# M3_Chip.net
KiCad netlist of a schematic drawn in Altium Designer
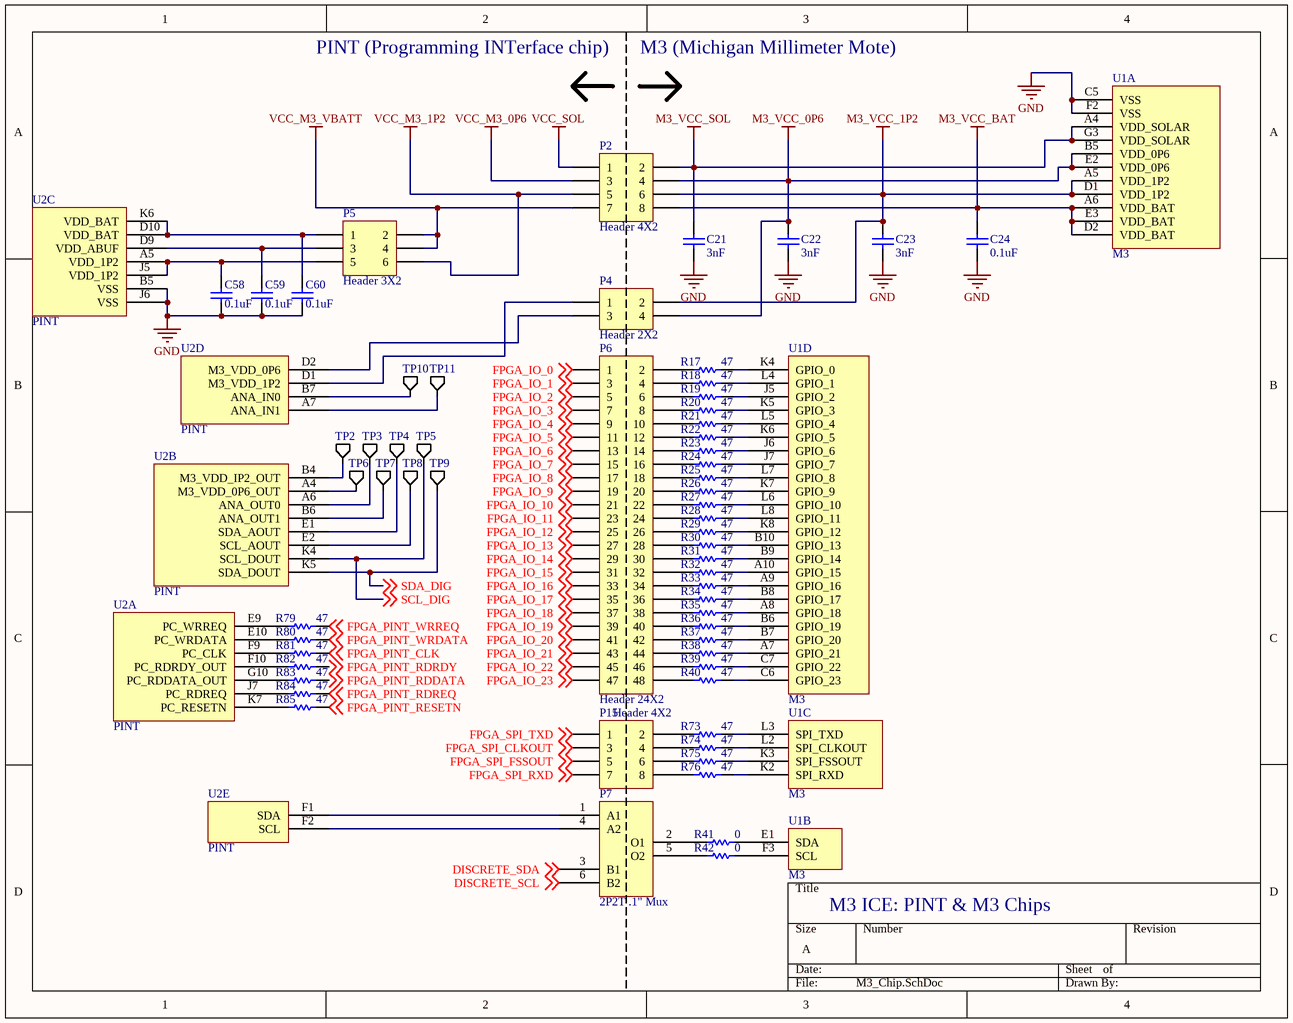
[diagram p0: M3_Chip.SchDoc]

(export (version "E")
  (design (tool "Eeschema 10.0.6"))
  (components
    (comp (ref "C21")
      (value "3nF")
      (footprint "1608[0603]")
      (description "Capacitor (Semiconductor SIM Model)")
      (fields
        (field (name "DISTPARTNO") "399-7893-1-ND")
        (field (name "MANPARTNO") "C0603C302K5GACTU")
        (field (name "PUBLISHER") "Altium Limited")
      )
      (libsource (lib "Miscellaneous Devices") (part "Cap Semi"))
    )
    (comp (ref "C22")
      (value "3nF")
      (footprint "1608[0603]")
      (description "Capacitor (Semiconductor SIM Model)")
      (fields
        (field (name "DISTPARTNO") "399-7893-1-ND")
        (field (name "MANPARTNO") "C0603C302K5GACTU")
        (field (name "PUBLISHER") "Altium Limited")
      )
      (libsource (lib "Miscellaneous Devices") (part "Cap Semi"))
    )
    (comp (ref "C23")
      (value "3nF")
      (footprint "1608[0603]")
      (description "Capacitor (Semiconductor SIM Model)")
      (fields
        (field (name "DISTPARTNO") "399-7893-1-ND")
        (field (name "MANPARTNO") "C0603C302K5GACTU")
        (field (name "PUBLISHER") "Altium Limited")
      )
      (libsource (lib "Miscellaneous Devices") (part "Cap Semi"))
    )
    (comp (ref "C24")
      (value "0.1uF")
      (footprint "1608[0603]")
      (description "Capacitor (Semiconductor SIM Model)")
      (fields
        (field (name "DISTPARTNO") "445-1317-1-ND")
        (field (name "MANPARTNO") "C1608X7R1C104K")
        (field (name "PUBLISHER") "Altium Limited")
      )
      (libsource (lib "Miscellaneous Devices") (part "Cap Semi"))
    )
    (comp (ref "C58")
      (value "0.1uF")
      (footprint "1608[0603]")
      (description "Capacitor (Semiconductor SIM Model)")
      (fields
        (field (name "DISTPARTNO") "445-1317-1-ND")
        (field (name "MANPARTNO") "C1608X7R1C104K")
        (field (name "PUBLISHER") "Altium Limited")
      )
      (libsource (lib "Miscellaneous Devices") (part "Cap Semi"))
    )
    (comp (ref "C59")
      (value "0.1uF")
      (footprint "1608[0603]")
      (description "Capacitor (Semiconductor SIM Model)")
      (fields
        (field (name "DISTPARTNO") "445-1317-1-ND")
        (field (name "MANPARTNO") "C1608X7R1C104K")
        (field (name "PUBLISHER") "Altium Limited")
      )
      (libsource (lib "Miscellaneous Devices") (part "Cap Semi"))
    )
    (comp (ref "C60")
      (value "0.1uF")
      (footprint "1608[0603]")
      (description "Capacitor (Semiconductor SIM Model)")
      (fields
        (field (name "DISTPARTNO") "445-1317-1-ND")
        (field (name "MANPARTNO") "C1608X7R1C104K")
        (field (name "PUBLISHER") "Altium Limited")
      )
      (libsource (lib "Miscellaneous Devices") (part "Cap Semi"))
    )
    (comp (ref "P2")
      (value "Header 4X2")
      (footprint "HDR2X4")
      (description "Header, 4-Pin, Dual row")
      (fields
        (field (name "DISTPARTNO") "A26530-40-ND")
        (field (name "MANPARTNO") "4-103328-0")
        (field (name "PUBLISHER") "Altium Limited")
      )
      (libsource (lib "Miscellaneous Connectors") (part "Header 4X2"))
    )
    (comp (ref "P4")
      (value "Header 2X2")
      (footprint "HDR2X2")
      (description "Header, 2-Pin, Dual row")
      (fields (field (name "PUBLISHER") "Altium Limited"))
      (libsource (lib "Miscellaneous Connectors") (part "Header 2X2"))
    )
    (comp (ref "P5")
      (value "Header 3X2")
      (footprint "HDR2X3")
      (description "Header, 3-Pin, Dual row")
      (fields (field (name "PUBLISHER") "Altium Limited"))
      (libsource (lib "Miscellaneous Connectors") (part "Header 3X2"))
    )
    (comp (ref "P6")
      (value "Header 24X2")
      (footprint "HDR2X24")
      (description "Header, 24-Pin, Dual row")
      (fields
        (field (name "DISTPARTNO") "A26530-40-ND")
        (field (name "MANPARTNO") "4-103328-0")
        (field (name "PUBLISHER") "Altium Limited")
      )
      (libsource (lib "Miscellaneous Connectors") (part "Header 24X2"))
    )
    (comp (ref "P7")
      (value "2P2T .1\" Mux")
      (footprint "HDR3x2")
      (libsource (lib "M3") (part "2P2T .1{dblquote} Mux"))
    )
    (comp (ref "P15")
      (value "Header 4X2")
      (footprint "HDR2X4")
      (description "Header, 4-Pin, Dual row")
      (fields (field (name "PUBLISHER") "Altium Limited"))
      (libsource (lib "Miscellaneous Connectors") (part "Header 4X2"))
    )
    (comp (ref "R17")
      (value "47")
      (footprint "0603")
      (description "Semiconductor Resistor")
      (fields
        (field (name "DISTPARTNO") "P47GCT-ND")
        (field (name "MANPARTNO") "ERJ-3GEYJ470V")
        (field (name "PUBLISHER") "Altium Limited")
      )
      (libsource (lib "M3") (part "Res Chip"))
    )
    (comp (ref "R18")
      (value "47")
      (footprint "0603")
      (description "Semiconductor Resistor")
      (fields
        (field (name "DISTPARTNO") "P47GCT-ND")
        (field (name "MANPARTNO") "ERJ-3GEYJ470V")
        (field (name "PUBLISHER") "Altium Limited")
      )
      (libsource (lib "M3") (part "Res Chip"))
    )
    (comp (ref "R19")
      (value "47")
      (footprint "0603")
      (description "Semiconductor Resistor")
      (fields
        (field (name "DISTPARTNO") "P47GCT-ND")
        (field (name "MANPARTNO") "ERJ-3GEYJ470V")
        (field (name "PUBLISHER") "Altium Limited")
      )
      (libsource (lib "M3") (part "Res Chip"))
    )
    (comp (ref "R20")
      (value "47")
      (footprint "0603")
      (description "Semiconductor Resistor")
      (fields
        (field (name "DISTPARTNO") "P47GCT-ND")
        (field (name "MANPARTNO") "ERJ-3GEYJ470V")
        (field (name "PUBLISHER") "Altium Limited")
      )
      (libsource (lib "M3") (part "Res Chip"))
    )
    (comp (ref "R21")
      (value "47")
      (footprint "0603")
      (description "Semiconductor Resistor")
      (fields
        (field (name "DISTPARTNO") "P47GCT-ND")
        (field (name "MANPARTNO") "ERJ-3GEYJ470V")
        (field (name "PUBLISHER") "Altium Limited")
      )
      (libsource (lib "M3") (part "Res Chip"))
    )
    (comp (ref "R22")
      (value "47")
      (footprint "0603")
      (description "Semiconductor Resistor")
      (fields
        (field (name "DISTPARTNO") "P47GCT-ND")
        (field (name "MANPARTNO") "ERJ-3GEYJ470V")
        (field (name "PUBLISHER") "Altium Limited")
      )
      (libsource (lib "M3") (part "Res Chip"))
    )
    (comp (ref "R23")
      (value "47")
      (footprint "0603")
      (description "Semiconductor Resistor")
      (fields
        (field (name "DISTPARTNO") "P47GCT-ND")
        (field (name "MANPARTNO") "ERJ-3GEYJ470V")
        (field (name "PUBLISHER") "Altium Limited")
      )
      (libsource (lib "M3") (part "Res Chip"))
    )
    (comp (ref "R24")
      (value "47")
      (footprint "0603")
      (description "Semiconductor Resistor")
      (fields
        (field (name "DISTPARTNO") "P47GCT-ND")
        (field (name "MANPARTNO") "ERJ-3GEYJ470V")
        (field (name "PUBLISHER") "Altium Limited")
      )
      (libsource (lib "M3") (part "Res Chip"))
    )
    (comp (ref "R25")
      (value "47")
      (footprint "0603")
      (description "Semiconductor Resistor")
      (fields
        (field (name "DISTPARTNO") "P47GCT-ND")
        (field (name "MANPARTNO") "ERJ-3GEYJ470V")
        (field (name "PUBLISHER") "Altium Limited")
      )
      (libsource (lib "M3") (part "Res Chip"))
    )
    (comp (ref "R26")
      (value "47")
      (footprint "0603")
      (description "Semiconductor Resistor")
      (fields
        (field (name "DISTPARTNO") "P47GCT-ND")
        (field (name "MANPARTNO") "ERJ-3GEYJ470V")
        (field (name "PUBLISHER") "Altium Limited")
      )
      (libsource (lib "M3") (part "Res Chip"))
    )
    (comp (ref "R27")
      (value "47")
      (footprint "0603")
      (description "Semiconductor Resistor")
      (fields
        (field (name "DISTPARTNO") "P47GCT-ND")
        (field (name "MANPARTNO") "ERJ-3GEYJ470V")
        (field (name "PUBLISHER") "Altium Limited")
      )
      (libsource (lib "M3") (part "Res Chip"))
    )
    (comp (ref "R28")
      (value "47")
      (footprint "0603")
      (description "Semiconductor Resistor")
      (fields
        (field (name "DISTPARTNO") "P47GCT-ND")
        (field (name "MANPARTNO") "ERJ-3GEYJ470V")
        (field (name "PUBLISHER") "Altium Limited")
      )
      (libsource (lib "M3") (part "Res Chip"))
    )
    (comp (ref "R29")
      (value "47")
      (footprint "0603")
      (description "Semiconductor Resistor")
      (fields
        (field (name "DISTPARTNO") "P47GCT-ND")
        (field (name "MANPARTNO") "ERJ-3GEYJ470V")
        (field (name "PUBLISHER") "Altium Limited")
      )
      (libsource (lib "M3") (part "Res Chip"))
    )
    (comp (ref "R30")
      (value "47")
      (footprint "0603")
      (description "Semiconductor Resistor")
      (fields
        (field (name "DISTPARTNO") "P47GCT-ND")
        (field (name "MANPARTNO") "ERJ-3GEYJ470V")
        (field (name "PUBLISHER") "Altium Limited")
      )
      (libsource (lib "M3") (part "Res Chip"))
    )
    (comp (ref "R31")
      (value "47")
      (footprint "0603")
      (description "Semiconductor Resistor")
      (fields
        (field (name "DISTPARTNO") "P47GCT-ND")
        (field (name "MANPARTNO") "ERJ-3GEYJ470V")
        (field (name "PUBLISHER") "Altium Limited")
      )
      (libsource (lib "M3") (part "Res Chip"))
    )
    (comp (ref "R32")
      (value "47")
      (footprint "0603")
      (description "Semiconductor Resistor")
      (fields
        (field (name "DISTPARTNO") "P47GCT-ND")
        (field (name "MANPARTNO") "ERJ-3GEYJ470V")
        (field (name "PUBLISHER") "Altium Limited")
      )
      (libsource (lib "M3") (part "Res Chip"))
    )
    (comp (ref "R33")
      (value "47")
      (footprint "0603")
      (description "Semiconductor Resistor")
      (fields
        (field (name "DISTPARTNO") "P47GCT-ND")
        (field (name "MANPARTNO") "ERJ-3GEYJ470V")
        (field (name "PUBLISHER") "Altium Limited")
      )
      (libsource (lib "M3") (part "Res Chip"))
    )
    (comp (ref "R34")
      (value "47")
      (footprint "0603")
      (description "Semiconductor Resistor")
      (fields
        (field (name "DISTPARTNO") "P47GCT-ND")
        (field (name "MANPARTNO") "ERJ-3GEYJ470V")
        (field (name "PUBLISHER") "Altium Limited")
      )
      (libsource (lib "M3") (part "Res Chip"))
    )
    (comp (ref "R35")
      (value "47")
      (footprint "0603")
      (description "Semiconductor Resistor")
      (fields
        (field (name "DISTPARTNO") "P47GCT-ND")
        (field (name "MANPARTNO") "ERJ-3GEYJ470V")
        (field (name "PUBLISHER") "Altium Limited")
      )
      (libsource (lib "M3") (part "Res Chip"))
    )
    (comp (ref "R36")
      (value "47")
      (footprint "0603")
      (description "Semiconductor Resistor")
      (fields
        (field (name "DISTPARTNO") "P47GCT-ND")
        (field (name "MANPARTNO") "ERJ-3GEYJ470V")
        (field (name "PUBLISHER") "Altium Limited")
      )
      (libsource (lib "M3") (part "Res Chip"))
    )
    (comp (ref "R37")
      (value "47")
      (footprint "0603")
      (description "Semiconductor Resistor")
      (fields
        (field (name "DISTPARTNO") "P47GCT-ND")
        (field (name "MANPARTNO") "ERJ-3GEYJ470V")
        (field (name "PUBLISHER") "Altium Limited")
      )
      (libsource (lib "M3") (part "Res Chip"))
    )
    (comp (ref "R38")
      (value "47")
      (footprint "0603")
      (description "Semiconductor Resistor")
      (fields
        (field (name "DISTPARTNO") "P47GCT-ND")
        (field (name "MANPARTNO") "ERJ-3GEYJ470V")
        (field (name "PUBLISHER") "Altium Limited")
      )
      (libsource (lib "M3") (part "Res Chip"))
    )
    (comp (ref "R39")
      (value "47")
      (footprint "0603")
      (description "Semiconductor Resistor")
      (fields
        (field (name "DISTPARTNO") "P47GCT-ND")
        (field (name "MANPARTNO") "ERJ-3GEYJ470V")
        (field (name "PUBLISHER") "Altium Limited")
      )
      (libsource (lib "M3") (part "Res Chip"))
    )
    (comp (ref "R40")
      (value "47")
      (footprint "0603")
      (description "Semiconductor Resistor")
      (fields
        (field (name "DISTPARTNO") "P47GCT-ND")
        (field (name "MANPARTNO") "ERJ-3GEYJ470V")
        (field (name "PUBLISHER") "Altium Limited")
      )
      (libsource (lib "M3") (part "Res Chip"))
    )
    (comp (ref "R41")
      (value "0")
      (footprint "0603")
      (description "Semiconductor Resistor")
      (fields
        (field (name "DISTPARTNO") "P0.0GCT-ND")
        (field (name "MANPARTNO") "ERJ-3GEY0R00V")
        (field (name "PUBLISHER") "Altium Limited")
      )
      (libsource (lib "M3") (part "Res Chip"))
    )
    (comp (ref "R42")
      (value "0")
      (footprint "0603")
      (description "Semiconductor Resistor")
      (fields
        (field (name "DISTPARTNO") "P0.0GCT-ND")
        (field (name "MANPARTNO") "ERJ-3GEY0R00V")
        (field (name "PUBLISHER") "Altium Limited")
      )
      (libsource (lib "M3") (part "Res Chip"))
    )
    (comp (ref "R73")
      (value "47")
      (footprint "0603")
      (description "Semiconductor Resistor")
      (fields
        (field (name "DISTPARTNO") "P47GCT-ND")
        (field (name "MANPARTNO") "ERJ-3GEYJ470V")
        (field (name "PUBLISHER") "Altium Limited")
      )
      (libsource (lib "M3") (part "Res Chip"))
    )
    (comp (ref "R74")
      (value "47")
      (footprint "0603")
      (description "Semiconductor Resistor")
      (fields
        (field (name "DISTPARTNO") "P47GCT-ND")
        (field (name "MANPARTNO") "ERJ-3GEYJ470V")
        (field (name "PUBLISHER") "Altium Limited")
      )
      (libsource (lib "M3") (part "Res Chip"))
    )
    (comp (ref "R75")
      (value "47")
      (footprint "0603")
      (description "Semiconductor Resistor")
      (fields
        (field (name "DISTPARTNO") "P47GCT-ND")
        (field (name "MANPARTNO") "ERJ-3GEYJ470V")
        (field (name "PUBLISHER") "Altium Limited")
      )
      (libsource (lib "M3") (part "Res Chip"))
    )
    (comp (ref "R76")
      (value "47")
      (footprint "0603")
      (description "Semiconductor Resistor")
      (fields
        (field (name "DISTPARTNO") "P47GCT-ND")
        (field (name "MANPARTNO") "ERJ-3GEYJ470V")
        (field (name "PUBLISHER") "Altium Limited")
      )
      (libsource (lib "M3") (part "Res Chip"))
    )
    (comp (ref "R79")
      (value "47")
      (footprint "0603")
      (description "Semiconductor Resistor")
      (fields
        (field (name "DISTPARTNO") "P47GCT-ND")
        (field (name "MANPARTNO") "ERJ-3GEYJ470V")
        (field (name "PUBLISHER") "Altium Limited")
      )
      (libsource (lib "M3") (part "Res Chip"))
    )
    (comp (ref "R80")
      (value "47")
      (footprint "0603")
      (description "Semiconductor Resistor")
      (fields
        (field (name "DISTPARTNO") "P47GCT-ND")
        (field (name "MANPARTNO") "ERJ-3GEYJ470V")
        (field (name "PUBLISHER") "Altium Limited")
      )
      (libsource (lib "M3") (part "Res Chip"))
    )
    (comp (ref "R81")
      (value "47")
      (footprint "0603")
      (description "Semiconductor Resistor")
      (fields
        (field (name "DISTPARTNO") "P47GCT-ND")
        (field (name "MANPARTNO") "ERJ-3GEYJ470V")
        (field (name "PUBLISHER") "Altium Limited")
      )
      (libsource (lib "M3") (part "Res Chip"))
    )
    (comp (ref "R82")
      (value "47")
      (footprint "0603")
      (description "Semiconductor Resistor")
      (fields
        (field (name "DISTPARTNO") "P47GCT-ND")
        (field (name "MANPARTNO") "ERJ-3GEYJ470V")
        (field (name "PUBLISHER") "Altium Limited")
      )
      (libsource (lib "M3") (part "Res Chip"))
    )
    (comp (ref "R83")
      (value "47")
      (footprint "0603")
      (description "Semiconductor Resistor")
      (fields
        (field (name "DISTPARTNO") "P47GCT-ND")
        (field (name "MANPARTNO") "ERJ-3GEYJ470V")
        (field (name "PUBLISHER") "Altium Limited")
      )
      (libsource (lib "M3") (part "Res Chip"))
    )
    (comp (ref "R84")
      (value "47")
      (footprint "0603")
      (description "Semiconductor Resistor")
      (fields
        (field (name "DISTPARTNO") "P47GCT-ND")
        (field (name "MANPARTNO") "ERJ-3GEYJ470V")
        (field (name "PUBLISHER") "Altium Limited")
      )
      (libsource (lib "M3") (part "Res Chip"))
    )
    (comp (ref "R85")
      (value "47")
      (footprint "0603")
      (description "Semiconductor Resistor")
      (fields
        (field (name "DISTPARTNO") "P47GCT-ND")
        (field (name "MANPARTNO") "ERJ-3GEYJ470V")
        (field (name "PUBLISHER") "Altium Limited")
      )
      (libsource (lib "M3") (part "Res Chip"))
    )
    (comp (ref "TP2") (value "TP") (footprint "TP") (libsource (lib "M3") (part "TP")))
    (comp (ref "TP3") (value "TP") (footprint "TP") (libsource (lib "M3") (part "TP")))
    (comp (ref "TP4") (value "TP") (footprint "TP") (libsource (lib "M3") (part "TP")))
    (comp (ref "TP5") (value "TP") (footprint "TP") (libsource (lib "M3") (part "TP")))
    (comp (ref "TP6") (value "TP") (footprint "TP") (libsource (lib "M3") (part "TP")))
    (comp (ref "TP7") (value "TP") (footprint "TP") (libsource (lib "M3") (part "TP")))
    (comp (ref "TP8") (value "TP") (footprint "TP") (libsource (lib "M3") (part "TP")))
    (comp (ref "TP9") (value "TP") (footprint "TP") (libsource (lib "M3") (part "TP")))
    (comp (ref "TP10") (value "TP") (footprint "TP") (libsource (lib "M3") (part "TP")))
    (comp (ref "TP11") (value "TP") (footprint "TP") (libsource (lib "M3") (part "TP")))
    (comp (ref "U1")
      (value "M3")
      (footprint "CPGA-84")
      (fields (field (name "DISTPARTNO") "3M5067-ND") (field (name "MANPARTNO") "200-6311-9UN-1900"))
      (libsource (lib "M3") (part "M3"))
    )
    (comp (ref "U2")
      (value "PINT")
      (footprint "CPGA-65")
      (fields (field (name "DISTPARTNO") "3M5066-ND") (field (name "MANPARTNO") "200-6310-9UN-1900"))
      (libsource (lib "M3") (part "PINT"))
    )
  )
  (nets
    (net (code "1") (name "DISCRETE_SCL") (class "Default")
      (node (ref "P7") (pin "6") (pinfunction "B2_6") (pintype "passive"))
    )
    (net (code "2") (name "DISCRETE_SDA") (class "Default")
      (node (ref "P7") (pin "3") (pinfunction "B1_3") (pintype "passive"))
    )
    (net (code "3") (name "FPGA_IO_0") (class "Default")
      (node (ref "P6") (pin "1") (pinfunction "1_1") (pintype "passive"))
    )
    (net (code "4") (name "FPGA_IO_1") (class "Default")
      (node (ref "P6") (pin "3") (pinfunction "3_3") (pintype "passive"))
    )
    (net (code "5") (name "FPGA_IO_2") (class "Default")
      (node (ref "P6") (pin "5") (pinfunction "5_5") (pintype "passive"))
    )
    (net (code "6") (name "FPGA_IO_3") (class "Default")
      (node (ref "P6") (pin "7") (pinfunction "7_7") (pintype "passive"))
    )
    (net (code "7") (name "FPGA_IO_4") (class "Default")
      (node (ref "P6") (pin "9") (pinfunction "9_9") (pintype "passive"))
    )
    (net (code "8") (name "FPGA_IO_5") (class "Default")
      (node (ref "P6") (pin "11") (pinfunction "11_11") (pintype "passive"))
    )
    (net (code "9") (name "FPGA_IO_6") (class "Default")
      (node (ref "P6") (pin "13") (pinfunction "13_13") (pintype "passive"))
    )
    (net (code "10") (name "FPGA_IO_7") (class "Default")
      (node (ref "P6") (pin "15") (pinfunction "15_15") (pintype "passive"))
    )
    (net (code "11") (name "FPGA_IO_8") (class "Default")
      (node (ref "P6") (pin "17") (pinfunction "17_17") (pintype "passive"))
    )
    (net (code "12") (name "FPGA_IO_9") (class "Default")
      (node (ref "P6") (pin "19") (pinfunction "19_19") (pintype "passive"))
    )
    (net (code "13") (name "FPGA_IO_10") (class "Default")
      (node (ref "P6") (pin "21") (pinfunction "21_21") (pintype "passive"))
    )
    (net (code "14") (name "FPGA_IO_11") (class "Default")
      (node (ref "P6") (pin "23") (pinfunction "23_23") (pintype "passive"))
    )
    (net (code "15") (name "FPGA_IO_12") (class "Default")
      (node (ref "P6") (pin "25") (pinfunction "25_25") (pintype "passive"))
    )
    (net (code "16") (name "FPGA_IO_13") (class "Default")
      (node (ref "P6") (pin "27") (pinfunction "27_27") (pintype "passive"))
    )
    (net (code "17") (name "FPGA_IO_14") (class "Default")
      (node (ref "P6") (pin "29") (pinfunction "29_29") (pintype "passive"))
    )
    (net (code "18") (name "FPGA_IO_15") (class "Default")
      (node (ref "P6") (pin "31") (pinfunction "31_31") (pintype "passive"))
    )
    (net (code "19") (name "FPGA_IO_16") (class "Default")
      (node (ref "P6") (pin "33") (pinfunction "33_33") (pintype "passive"))
    )
    (net (code "20") (name "FPGA_IO_17") (class "Default")
      (node (ref "P6") (pin "35") (pinfunction "35_35") (pintype "passive"))
    )
    (net (code "21") (name "FPGA_IO_18") (class "Default")
      (node (ref "P6") (pin "37") (pinfunction "37_37") (pintype "passive"))
    )
    (net (code "22") (name "FPGA_IO_19") (class "Default")
      (node (ref "P6") (pin "39") (pinfunction "39_39") (pintype "passive"))
    )
    (net (code "23") (name "FPGA_IO_20") (class "Default")
      (node (ref "P6") (pin "41") (pinfunction "41_41") (pintype "passive"))
    )
    (net (code "24") (name "FPGA_IO_21") (class "Default")
      (node (ref "P6") (pin "43") (pinfunction "43_43") (pintype "passive"))
    )
    (net (code "25") (name "FPGA_IO_22") (class "Default")
      (node (ref "P6") (pin "45") (pinfunction "45_45") (pintype "passive"))
    )
    (net (code "26") (name "FPGA_IO_23") (class "Default")
      (node (ref "P6") (pin "47") (pinfunction "47_47") (pintype "passive"))
    )
    (net (code "27") (name "FPGA_PINT_CLK") (class "Default")
      (node (ref "R81") (pin "1") (pinfunction "1_1") (pintype "passive"))
    )
    (net (code "28") (name "FPGA_PINT_RDDATA") (class "Default")
      (node (ref "R83") (pin "1") (pinfunction "1_1") (pintype "passive"))
    )
    (net (code "29") (name "FPGA_PINT_RDRDY") (class "Default")
      (node (ref "R82") (pin "1") (pinfunction "1_1") (pintype "passive"))
    )
    (net (code "30") (name "FPGA_PINT_RDREQ") (class "Default")
      (node (ref "R84") (pin "1") (pinfunction "1_1") (pintype "passive"))
    )
    (net (code "31") (name "FPGA_PINT_RESETN") (class "Default")
      (node (ref "R85") (pin "1") (pinfunction "1_1") (pintype "passive"))
    )
    (net (code "32") (name "FPGA_PINT_WRDATA") (class "Default")
      (node (ref "R80") (pin "1") (pinfunction "1_1") (pintype "passive"))
    )
    (net (code "33") (name "FPGA_PINT_WRREQ") (class "Default")
      (node (ref "R79") (pin "1") (pinfunction "1_1") (pintype "passive"))
    )
    (net (code "34") (name "FPGA_SPI_CLKOUT") (class "Default")
      (node (ref "P15") (pin "3") (pinfunction "3_3") (pintype "passive"))
    )
    (net (code "35") (name "FPGA_SPI_FSSOUT") (class "Default")
      (node (ref "P15") (pin "5") (pinfunction "5_5") (pintype "passive"))
    )
    (net (code "36") (name "FPGA_SPI_RXD") (class "Default")
      (node (ref "P15") (pin "7") (pinfunction "7_7") (pintype "passive"))
    )
    (net (code "37") (name "FPGA_SPI_TXD") (class "Default")
      (node (ref "P15") (pin "1") (pinfunction "1_1") (pintype "passive"))
    )
    (net (code "38") (name "GND") (class "Default")
      (node (ref "C21") (pin "1") (pinfunction "1_1") (pintype "passive"))
      (node (ref "C22") (pin "1") (pinfunction "1_1") (pintype "passive"))
      (node (ref "C23") (pin "1") (pinfunction "1_1") (pintype "passive"))
      (node (ref "C24") (pin "1") (pinfunction "1_1") (pintype "passive"))
      (node (ref "C58") (pin "1") (pinfunction "1_1") (pintype "passive"))
      (node (ref "C59") (pin "1") (pinfunction "1_1") (pintype "passive"))
      (node (ref "C60") (pin "1") (pinfunction "1_1") (pintype "passive"))
      (node (ref "U1") (pin "C5") (pinfunction "VSS_C5") (pintype "passive"))
      (node (ref "U1") (pin "F2") (pinfunction "VSS_F2") (pintype "passive"))
      (node (ref "U2") (pin "B5") (pinfunction "VSS_B5") (pintype "passive"))
      (node (ref "U2") (pin "J6") (pinfunction "VSS_J6") (pintype "passive"))
    )
    (net (code "39") (name "M3_VCC_0P6") (class "Default")
      (node (ref "C22") (pin "2") (pinfunction "2_2") (pintype "passive"))
      (node (ref "P2") (pin "4") (pinfunction "4_4") (pintype "passive"))
      (node (ref "P4") (pin "4") (pinfunction "4_4") (pintype "passive"))
      (node (ref "U1") (pin "B5") (pinfunction "VDD_0P6_B5") (pintype "passive"))
      (node (ref "U1") (pin "E2") (pinfunction "VDD_0P6_E2") (pintype "passive"))
    )
    (net (code "40") (name "M3_VCC_1P2") (class "Default")
      (node (ref "C23") (pin "2") (pinfunction "2_2") (pintype "passive"))
      (node (ref "P2") (pin "6") (pinfunction "6_6") (pintype "passive"))
      (node (ref "P4") (pin "2") (pinfunction "2_2") (pintype "passive"))
      (node (ref "U1") (pin "A5") (pinfunction "VDD_1P2_A5") (pintype "passive"))
      (node (ref "U1") (pin "D1") (pinfunction "VDD_1P2_D1") (pintype "passive"))
    )
    (net (code "41") (name "M3_VCC_BAT") (class "Default")
      (node (ref "C24") (pin "2") (pinfunction "2_2") (pintype "passive"))
      (node (ref "P2") (pin "8") (pinfunction "8_8") (pintype "passive"))
      (node (ref "U1") (pin "A6") (pinfunction "VDD_BAT_A6") (pintype "passive"))
      (node (ref "U1") (pin "D2") (pinfunction "VDD_BAT_D2") (pintype "passive"))
      (node (ref "U1") (pin "E3") (pinfunction "VDD_BAT_E3") (pintype "passive"))
    )
    (net (code "42") (name "M3_VCC_SOL") (class "Default")
      (node (ref "C21") (pin "2") (pinfunction "2_2") (pintype "passive"))
      (node (ref "P2") (pin "2") (pinfunction "2_2") (pintype "passive"))
      (node (ref "U1") (pin "A4") (pinfunction "VDD_SOLAR_A4") (pintype "passive"))
      (node (ref "U1") (pin "G3") (pinfunction "VDD_SOLAR_G3") (pintype "passive"))
    )
    (net (code "43") (name "Net-(C58-Pad2)") (class "Default")
      (node (ref "C58") (pin "2") (pinfunction "2_2") (pintype "passive"))
      (node (ref "P5") (pin "5") (pinfunction "5_5") (pintype "passive"))
      (node (ref "U2") (pin "A5") (pinfunction "VDD_1P2_A5") (pintype "passive"))
      (node (ref "U2") (pin "J5") (pinfunction "VDD_1P2_J5") (pintype "passive"))
    )
    (net (code "44") (name "Net-(C60-Pad2)") (class "Default")
      (node (ref "C60") (pin "2") (pinfunction "2_2") (pintype "passive"))
      (node (ref "P5") (pin "1") (pinfunction "1_1") (pintype "passive"))
      (node (ref "U2") (pin "D10") (pinfunction "VDD_BAT_D10") (pintype "passive"))
      (node (ref "U2") (pin "K6") (pinfunction "VDD_BAT_K6") (pintype "passive"))
    )
    (net (code "45") (name "Net-(P6-Pad2)") (class "Default")
      (node (ref "P6") (pin "2") (pinfunction "2_2") (pintype "passive"))
      (node (ref "R17") (pin "2") (pinfunction "2_2") (pintype "passive"))
    )
    (net (code "46") (name "Net-(P6-Pad4)") (class "Default")
      (node (ref "P6") (pin "4") (pinfunction "4_4") (pintype "passive"))
      (node (ref "R18") (pin "2") (pinfunction "2_2") (pintype "passive"))
    )
    (net (code "47") (name "Net-(P6-Pad6)") (class "Default")
      (node (ref "P6") (pin "6") (pinfunction "6_6") (pintype "passive"))
      (node (ref "R19") (pin "2") (pinfunction "2_2") (pintype "passive"))
    )
    (net (code "48") (name "Net-(P6-Pad8)") (class "Default")
      (node (ref "P6") (pin "8") (pinfunction "8_8") (pintype "passive"))
      (node (ref "R20") (pin "2") (pinfunction "2_2") (pintype "passive"))
    )
    (net (code "49") (name "Net-(P6-Pad10)") (class "Default")
      (node (ref "P6") (pin "10") (pinfunction "10_10") (pintype "passive"))
      (node (ref "R21") (pin "2") (pinfunction "2_2") (pintype "passive"))
    )
    (net (code "50") (name "Net-(P6-Pad12)") (class "Default")
      (node (ref "P6") (pin "12") (pinfunction "12_12") (pintype "passive"))
      (node (ref "R22") (pin "2") (pinfunction "2_2") (pintype "passive"))
    )
    (net (code "51") (name "Net-(P6-Pad14)") (class "Default")
      (node (ref "P6") (pin "14") (pinfunction "14_14") (pintype "passive"))
      (node (ref "R23") (pin "2") (pinfunction "2_2") (pintype "passive"))
    )
    (net (code "52") (name "Net-(P6-Pad16)") (class "Default")
      (node (ref "P6") (pin "16") (pinfunction "16_16") (pintype "passive"))
      (node (ref "R24") (pin "2") (pinfunction "2_2") (pintype "passive"))
    )
    (net (code "53") (name "Net-(P6-Pad18)") (class "Default")
      (node (ref "P6") (pin "18") (pinfunction "18_18") (pintype "passive"))
      (node (ref "R25") (pin "2") (pinfunction "2_2") (pintype "passive"))
    )
    (net (code "54") (name "Net-(P6-Pad20)") (class "Default")
      (node (ref "P6") (pin "20") (pinfunction "20_20") (pintype "passive"))
      (node (ref "R26") (pin "2") (pinfunction "2_2") (pintype "passive"))
    )
    (net (code "55") (name "Net-(P6-Pad22)") (class "Default")
      (node (ref "P6") (pin "22") (pinfunction "22_22") (pintype "passive"))
      (node (ref "R27") (pin "2") (pinfunction "2_2") (pintype "passive"))
    )
    (net (code "56") (name "Net-(P6-Pad24)") (class "Default")
      (node (ref "P6") (pin "24") (pinfunction "24_24") (pintype "passive"))
      (node (ref "R28") (pin "2") (pinfunction "2_2") (pintype "passive"))
    )
    (net (code "57") (name "Net-(P6-Pad26)") (class "Default")
      (node (ref "P6") (pin "26") (pinfunction "26_26") (pintype "passive"))
      (node (ref "R29") (pin "2") (pinfunction "2_2") (pintype "passive"))
    )
    (net (code "58") (name "Net-(P6-Pad28)") (class "Default")
      (node (ref "P6") (pin "28") (pinfunction "28_28") (pintype "passive"))
      (node (ref "R30") (pin "2") (pinfunction "2_2") (pintype "passive"))
    )
    (net (code "59") (name "Net-(P6-Pad30)") (class "Default")
      (node (ref "P6") (pin "30") (pinfunction "30_30") (pintype "passive"))
      (node (ref "R31") (pin "2") (pinfunction "2_2") (pintype "passive"))
    )
    (net (code "60") (name "Net-(P6-Pad32)") (class "Default")
      (node (ref "P6") (pin "32") (pinfunction "32_32") (pintype "passive"))
      (node (ref "R32") (pin "2") (pinfunction "2_2") (pintype "passive"))
    )
    (net (code "61") (name "Net-(P6-Pad34)") (class "Default")
      (node (ref "P6") (pin "34") (pinfunction "34_34") (pintype "passive"))
      (node (ref "R33") (pin "2") (pinfunction "2_2") (pintype "passive"))
    )
    (net (code "62") (name "Net-(P6-Pad36)") (class "Default")
      (node (ref "P6") (pin "36") (pinfunction "36_36") (pintype "passive"))
      (node (ref "R34") (pin "2") (pinfunction "2_2") (pintype "passive"))
    )
    (net (code "63") (name "Net-(P6-Pad38)") (class "Default")
      (node (ref "P6") (pin "38") (pinfunction "38_38") (pintype "passive"))
      (node (ref "R35") (pin "2") (pinfunction "2_2") (pintype "passive"))
    )
    (net (code "64") (name "Net-(P6-Pad40)") (class "Default")
      (node (ref "P6") (pin "40") (pinfunction "40_40") (pintype "passive"))
      (node (ref "R36") (pin "2") (pinfunction "2_2") (pintype "passive"))
    )
    (net (code "65") (name "Net-(P6-Pad42)") (class "Default")
      (node (ref "P6") (pin "42") (pinfunction "42_42") (pintype "passive"))
      (node (ref "R37") (pin "2") (pinfunction "2_2") (pintype "passive"))
    )
    (net (code "66") (name "Net-(P6-Pad44)") (class "Default")
      (node (ref "P6") (pin "44") (pinfunction "44_44") (pintype "passive"))
      (node (ref "R38") (pin "2") (pinfunction "2_2") (pintype "passive"))
    )
    (net (code "67") (name "Net-(P6-Pad46)") (class "Default")
      (node (ref "P6") (pin "46") (pinfunction "46_46") (pintype "passive"))
      (node (ref "R39") (pin "2") (pinfunction "2_2") (pintype "passive"))
    )
    (net (code "68") (name "Net-(P6-Pad48)") (class "Default")
      (node (ref "P6") (pin "48") (pinfunction "48_48") (pintype "passive"))
      (node (ref "R40") (pin "2") (pinfunction "2_2") (pintype "passive"))
    )
    (net (code "69") (name "Net-(P7-A1)") (class "Default")
      (node (ref "P7") (pin "1") (pinfunction "A1_1") (pintype "passive"))
      (node (ref "U2") (pin "F1") (pinfunction "SDA_F1") (pintype "passive"))
    )
    (net (code "70") (name "Net-(P7-A2)") (class "Default")
      (node (ref "P7") (pin "4") (pinfunction "A2_4") (pintype "passive"))
      (node (ref "U2") (pin "F2") (pinfunction "SCL_F2") (pintype "passive"))
    )
    (net (code "71") (name "Net-(P7-O1)") (class "Default")
      (node (ref "P7") (pin "2") (pinfunction "O1_2") (pintype "passive"))
      (node (ref "R41") (pin "2") (pinfunction "2_2") (pintype "passive"))
    )
    (net (code "72") (name "Net-(P7-O2)") (class "Default")
      (node (ref "P7") (pin "5") (pinfunction "O2_5") (pintype "passive"))
      (node (ref "R42") (pin "2") (pinfunction "2_2") (pintype "passive"))
    )
    (net (code "73") (name "Net-(P15-Pad2)") (class "Default")
      (node (ref "P15") (pin "2") (pinfunction "2_2") (pintype "passive"))
      (node (ref "R73") (pin "2") (pinfunction "2_2") (pintype "passive"))
    )
    (net (code "74") (name "Net-(P15-Pad4)") (class "Default")
      (node (ref "P15") (pin "4") (pinfunction "4_4") (pintype "passive"))
      (node (ref "R74") (pin "2") (pinfunction "2_2") (pintype "passive"))
    )
    (net (code "75") (name "Net-(P15-Pad6)") (class "Default")
      (node (ref "P15") (pin "6") (pinfunction "6_6") (pintype "passive"))
      (node (ref "R75") (pin "2") (pinfunction "2_2") (pintype "passive"))
    )
    (net (code "76") (name "Net-(P15-Pad8)") (class "Default")
      (node (ref "P15") (pin "8") (pinfunction "8_8") (pintype "passive"))
      (node (ref "R76") (pin "2") (pinfunction "2_2") (pintype "passive"))
    )
    (net (code "77") (name "Net-(TP2-A)") (class "Default")
      (node (ref "TP2") (pin "1") (pinfunction "A_1") (pintype "passive"))
      (node (ref "U2") (pin "B4") (pinfunction "M3_VDD_IP2_OUT_B4") (pintype "passive"))
    )
    (net (code "78") (name "Net-(TP3-A)") (class "Default")
      (node (ref "TP3") (pin "1") (pinfunction "A_1") (pintype "passive"))
      (node (ref "U2") (pin "A6") (pinfunction "ANA_OUT0_A6") (pintype "passive"))
    )
    (net (code "79") (name "Net-(TP4-A)") (class "Default")
      (node (ref "TP4") (pin "1") (pinfunction "A_1") (pintype "passive"))
      (node (ref "U2") (pin "E1") (pinfunction "SDA_AOUT_E1") (pintype "passive"))
    )
    (net (code "80") (name "Net-(TP6-A)") (class "Default")
      (node (ref "TP6") (pin "1") (pinfunction "A_1") (pintype "passive"))
      (node (ref "U2") (pin "A4") (pinfunction "M3_VDD_0P6_OUT_A4") (pintype "passive"))
    )
    (net (code "81") (name "Net-(TP7-A)") (class "Default")
      (node (ref "TP7") (pin "1") (pinfunction "A_1") (pintype "passive"))
      (node (ref "U2") (pin "B6") (pinfunction "ANA_OUT1_B6") (pintype "passive"))
    )
    (net (code "82") (name "Net-(TP8-A)") (class "Default")
      (node (ref "TP8") (pin "1") (pinfunction "A_1") (pintype "passive"))
      (node (ref "U2") (pin "E2") (pinfunction "SCL_AOUT_E2") (pintype "passive"))
    )
    (net (code "83") (name "Net-(TP10-A)") (class "Default")
      (node (ref "TP10") (pin "1") (pinfunction "A_1") (pintype "passive"))
      (node (ref "U2") (pin "B7") (pinfunction "ANA_IN0_B7") (pintype "passive"))
    )
    (net (code "84") (name "Net-(TP11-A)") (class "Default")
      (node (ref "TP11") (pin "1") (pinfunction "A_1") (pintype "passive"))
      (node (ref "U2") (pin "A7") (pinfunction "ANA_IN1_A7") (pintype "passive"))
    )
    (net (code "85") (name "Net-(U1B-SCL)") (class "Default")
      (node (ref "R42") (pin "1") (pinfunction "1_1") (pintype "passive"))
      (node (ref "U1") (pin "F3") (pinfunction "SCL_F3") (pintype "passive"))
    )
    (net (code "86") (name "Net-(U1B-SDA)") (class "Default")
      (node (ref "R41") (pin "1") (pinfunction "1_1") (pintype "passive"))
      (node (ref "U1") (pin "E1") (pinfunction "SDA_E1") (pintype "passive"))
    )
    (net (code "87") (name "Net-(U1C-SPI_CLKOUT)") (class "Default")
      (node (ref "R74") (pin "1") (pinfunction "1_1") (pintype "passive"))
      (node (ref "U1") (pin "L2") (pinfunction "SPI_CLKOUT_L2") (pintype "passive"))
    )
    (net (code "88") (name "Net-(U1C-SPI_FSSOUT)") (class "Default")
      (node (ref "R75") (pin "1") (pinfunction "1_1") (pintype "passive"))
      (node (ref "U1") (pin "K3") (pinfunction "SPI_FSSOUT_K3") (pintype "passive"))
    )
    (net (code "89") (name "Net-(U1C-SPI_RXD)") (class "Default")
      (node (ref "R76") (pin "1") (pinfunction "1_1") (pintype "passive"))
      (node (ref "U1") (pin "K2") (pinfunction "SPI_RXD_K2") (pintype "passive"))
    )
    (net (code "90") (name "Net-(U1C-SPI_TXD)") (class "Default")
      (node (ref "R73") (pin "1") (pinfunction "1_1") (pintype "passive"))
      (node (ref "U1") (pin "L3") (pinfunction "SPI_TXD_L3") (pintype "passive"))
    )
    (net (code "91") (name "Net-(U1D-GPIO_0)") (class "Default")
      (node (ref "R17") (pin "1") (pinfunction "1_1") (pintype "passive"))
      (node (ref "U1") (pin "K4") (pinfunction "GPIO_0_K4") (pintype "passive"))
    )
    (net (code "92") (name "Net-(U1D-GPIO_1)") (class "Default")
      (node (ref "R18") (pin "1") (pinfunction "1_1") (pintype "passive"))
      (node (ref "U1") (pin "L4") (pinfunction "GPIO_1_L4") (pintype "passive"))
    )
    (net (code "93") (name "Net-(U1D-GPIO_2)") (class "Default")
      (node (ref "R19") (pin "1") (pinfunction "1_1") (pintype "passive"))
      (node (ref "U1") (pin "J5") (pinfunction "GPIO_2_J5") (pintype "passive"))
    )
    (net (code "94") (name "Net-(U1D-GPIO_3)") (class "Default")
      (node (ref "R20") (pin "1") (pinfunction "1_1") (pintype "passive"))
      (node (ref "U1") (pin "K5") (pinfunction "GPIO_3_K5") (pintype "passive"))
    )
    (net (code "95") (name "Net-(U1D-GPIO_4)") (class "Default")
      (node (ref "R21") (pin "1") (pinfunction "1_1") (pintype "passive"))
      (node (ref "U1") (pin "L5") (pinfunction "GPIO_4_L5") (pintype "passive"))
    )
    (net (code "96") (name "Net-(U1D-GPIO_5)") (class "Default")
      (node (ref "R22") (pin "1") (pinfunction "1_1") (pintype "passive"))
      (node (ref "U1") (pin "K6") (pinfunction "GPIO_5_K6") (pintype "passive"))
    )
    (net (code "97") (name "Net-(U1D-GPIO_6)") (class "Default")
      (node (ref "R23") (pin "1") (pinfunction "1_1") (pintype "passive"))
      (node (ref "U1") (pin "J6") (pinfunction "GPIO_6_J6") (pintype "passive"))
    )
    (net (code "98") (name "Net-(U1D-GPIO_7)") (class "Default")
      (node (ref "R24") (pin "1") (pinfunction "1_1") (pintype "passive"))
      (node (ref "U1") (pin "J7") (pinfunction "GPIO_7_J7") (pintype "passive"))
    )
    (net (code "99") (name "Net-(U1D-GPIO_8)") (class "Default")
      (node (ref "R25") (pin "1") (pinfunction "1_1") (pintype "passive"))
      (node (ref "U1") (pin "L7") (pinfunction "GPIO_8_L7") (pintype "passive"))
    )
    (net (code "100") (name "Net-(U1D-GPIO_9)") (class "Default")
      (node (ref "R26") (pin "1") (pinfunction "1_1") (pintype "passive"))
      (node (ref "U1") (pin "K7") (pinfunction "GPIO_9_K7") (pintype "passive"))
    )
    (net (code "101") (name "Net-(U1D-GPIO_10)") (class "Default")
      (node (ref "R27") (pin "1") (pinfunction "1_1") (pintype "passive"))
      (node (ref "U1") (pin "L6") (pinfunction "GPIO_10_L6") (pintype "passive"))
    )
    (net (code "102") (name "Net-(U1D-GPIO_11)") (class "Default")
      (node (ref "R28") (pin "1") (pinfunction "1_1") (pintype "passive"))
      (node (ref "U1") (pin "L8") (pinfunction "GPIO_11_L8") (pintype "passive"))
    )
    (net (code "103") (name "Net-(U1D-GPIO_12)") (class "Default")
      (node (ref "R29") (pin "1") (pinfunction "1_1") (pintype "passive"))
      (node (ref "U1") (pin "K8") (pinfunction "GPIO_12_K8") (pintype "passive"))
    )
    (net (code "104") (name "Net-(U1D-GPIO_13)") (class "Default")
      (node (ref "R30") (pin "1") (pinfunction "1_1") (pintype "passive"))
      (node (ref "U1") (pin "B10") (pinfunction "GPIO_13_B10") (pintype "passive"))
    )
    (net (code "105") (name "Net-(U1D-GPIO_14)") (class "Default")
      (node (ref "R31") (pin "1") (pinfunction "1_1") (pintype "passive"))
      (node (ref "U1") (pin "B9") (pinfunction "GPIO_14_B9") (pintype "passive"))
    )
    (net (code "106") (name "Net-(U1D-GPIO_15)") (class "Default")
      (node (ref "R32") (pin "1") (pinfunction "1_1") (pintype "passive"))
      (node (ref "U1") (pin "A10") (pinfunction "GPIO_15_A10") (pintype "passive"))
    )
    (net (code "107") (name "Net-(U1D-GPIO_16)") (class "Default")
      (node (ref "R33") (pin "1") (pinfunction "1_1") (pintype "passive"))
      (node (ref "U1") (pin "A9") (pinfunction "GPIO_16_A9") (pintype "passive"))
    )
    (net (code "108") (name "Net-(U1D-GPIO_17)") (class "Default")
      (node (ref "R34") (pin "1") (pinfunction "1_1") (pintype "passive"))
      (node (ref "U1") (pin "B8") (pinfunction "GPIO_17_B8") (pintype "passive"))
    )
    (net (code "109") (name "Net-(U1D-GPIO_18)") (class "Default")
      (node (ref "R35") (pin "1") (pinfunction "1_1") (pintype "passive"))
      (node (ref "U1") (pin "A8") (pinfunction "GPIO_18_A8") (pintype "passive"))
    )
    (net (code "110") (name "Net-(U1D-GPIO_19)") (class "Default")
      (node (ref "R36") (pin "1") (pinfunction "1_1") (pintype "passive"))
      (node (ref "U1") (pin "B6") (pinfunction "GPIO_19_B6") (pintype "passive"))
    )
    (net (code "111") (name "Net-(U1D-GPIO_20)") (class "Default")
      (node (ref "R37") (pin "1") (pinfunction "1_1") (pintype "passive"))
      (node (ref "U1") (pin "B7") (pinfunction "GPIO_20_B7") (pintype "passive"))
    )
    (net (code "112") (name "Net-(U1D-GPIO_21)") (class "Default")
      (node (ref "R38") (pin "1") (pinfunction "1_1") (pintype "passive"))
      (node (ref "U1") (pin "A7") (pinfunction "GPIO_21_A7") (pintype "passive"))
    )
    (net (code "113") (name "Net-(U1D-GPIO_22)") (class "Default")
      (node (ref "R39") (pin "1") (pinfunction "1_1") (pintype "passive"))
      (node (ref "U1") (pin "C7") (pinfunction "GPIO_22_C7") (pintype "passive"))
    )
    (net (code "114") (name "Net-(U1D-GPIO_23)") (class "Default")
      (node (ref "R40") (pin "1") (pinfunction "1_1") (pintype "passive"))
      (node (ref "U1") (pin "C6") (pinfunction "GPIO_23_C6") (pintype "passive"))
    )
    (net (code "115") (name "Net-(U2A-PC_CLK)") (class "Default")
      (node (ref "R81") (pin "2") (pinfunction "2_2") (pintype "passive"))
      (node (ref "U2") (pin "F9") (pinfunction "PC_CLK_F9") (pintype "passive"))
    )
    (net (code "116") (name "Net-(U2A-PC_RDDATA_OUT)") (class "Default")
      (node (ref "R83") (pin "2") (pinfunction "2_2") (pintype "passive"))
      (node (ref "U2") (pin "G10") (pinfunction "PC_RDDATA_OUT_G10") (pintype "passive"))
    )
    (net (code "117") (name "Net-(U2A-PC_RDRDY_OUT)") (class "Default")
      (node (ref "R82") (pin "2") (pinfunction "2_2") (pintype "passive"))
      (node (ref "U2") (pin "F10") (pinfunction "PC_RDRDY_OUT_F10") (pintype "passive"))
    )
    (net (code "118") (name "Net-(U2A-PC_RDREQ)") (class "Default")
      (node (ref "R84") (pin "2") (pinfunction "2_2") (pintype "passive"))
      (node (ref "U2") (pin "J7") (pinfunction "PC_RDREQ_J7") (pintype "passive"))
    )
    (net (code "119") (name "Net-(U2A-PC_RESETN)") (class "Default")
      (node (ref "R85") (pin "2") (pinfunction "2_2") (pintype "passive"))
      (node (ref "U2") (pin "K7") (pinfunction "PC_RESETN_K7") (pintype "passive"))
    )
    (net (code "120") (name "Net-(U2A-PC_WRDATA)") (class "Default")
      (node (ref "R80") (pin "2") (pinfunction "2_2") (pintype "passive"))
      (node (ref "U2") (pin "E10") (pinfunction "PC_WRDATA_E10") (pintype "passive"))
    )
    (net (code "121") (name "Net-(U2A-PC_WRREQ)") (class "Default")
      (node (ref "R79") (pin "2") (pinfunction "2_2") (pintype "passive"))
      (node (ref "U2") (pin "E9") (pinfunction "PC_WRREQ_E9") (pintype "passive"))
    )
    (net (code "122") (name "Net-(U2C-VDD_ABUF)") (class "Default")
      (node (ref "C59") (pin "2") (pinfunction "2_2") (pintype "passive"))
      (node (ref "P5") (pin "3") (pinfunction "3_3") (pintype "passive"))
      (node (ref "U2") (pin "D9") (pinfunction "VDD_ABUF_D9") (pintype "passive"))
    )
    (net (code "123") (name "Net-(U2D-M3_VDD_0P6)") (class "Default")
      (node (ref "P4") (pin "3") (pinfunction "3_3") (pintype "passive"))
      (node (ref "U2") (pin "D2") (pinfunction "M3_VDD_0P6_D2") (pintype "passive"))
    )
    (net (code "124") (name "Net-(U2D-M3_VDD_1P2)") (class "Default")
      (node (ref "P4") (pin "1") (pinfunction "1_1") (pintype "passive"))
      (node (ref "U2") (pin "D1") (pinfunction "M3_VDD_1P2_D1") (pintype "passive"))
    )
    (net (code "125") (name "SCL_DIG") (class "Default")
      (node (ref "TP5") (pin "1") (pinfunction "A_1") (pintype "passive"))
      (node (ref "U2") (pin "K4") (pinfunction "SCL_DOUT_K4") (pintype "passive"))
    )
    (net (code "126") (name "SDA_DIG") (class "Default")
      (node (ref "TP9") (pin "1") (pinfunction "A_1") (pintype "passive"))
      (node (ref "U2") (pin "K5") (pinfunction "SDA_DOUT_K5") (pintype "passive"))
    )
    (net (code "127") (name "VCC_M3_0P6") (class "Default")
      (node (ref "P2") (pin "3") (pinfunction "3_3") (pintype "passive"))
    )
    (net (code "128") (name "VCC_M3_1P2") (class "Default")
      (node (ref "P2") (pin "5") (pinfunction "5_5") (pintype "passive"))
      (node (ref "P5") (pin "6") (pinfunction "6_6") (pintype "passive"))
    )
    (net (code "129") (name "VCC_M3_VBATT") (class "Default")
      (node (ref "P2") (pin "7") (pinfunction "7_7") (pintype "passive"))
      (node (ref "P5") (pin "2") (pinfunction "2_2") (pintype "passive"))
      (node (ref "P5") (pin "4") (pinfunction "4_4") (pintype "passive"))
    )
    (net (code "130") (name "VCC_SOL") (class "Default")
      (node (ref "P2") (pin "1") (pinfunction "1_1") (pintype "passive"))
    )
  )
)
